# SparkFun_CAN-Bus_Shield.net
KiCad netlist of a schematic drawn in EAGLE
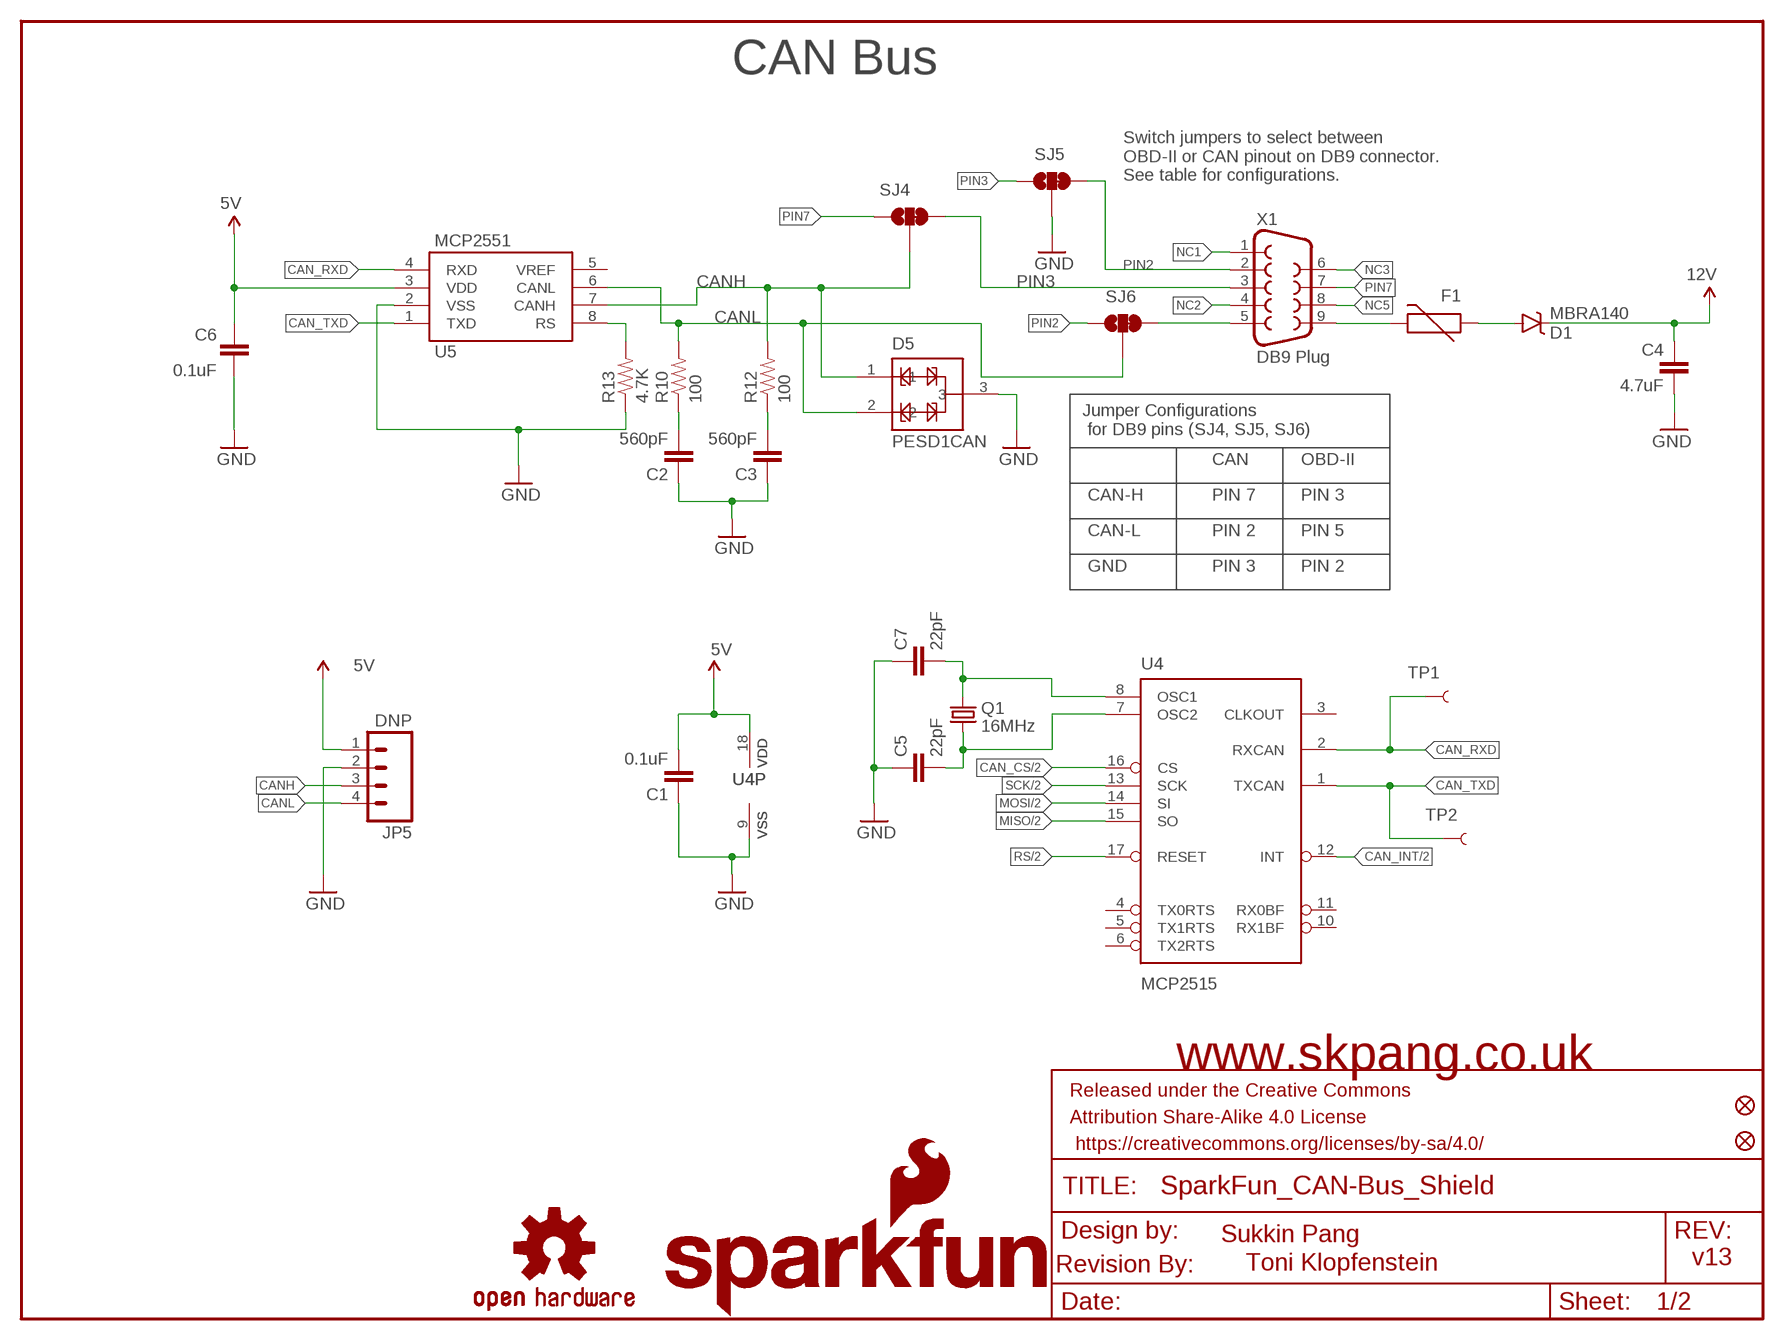
[diagram p0: schematic, sheet 1]
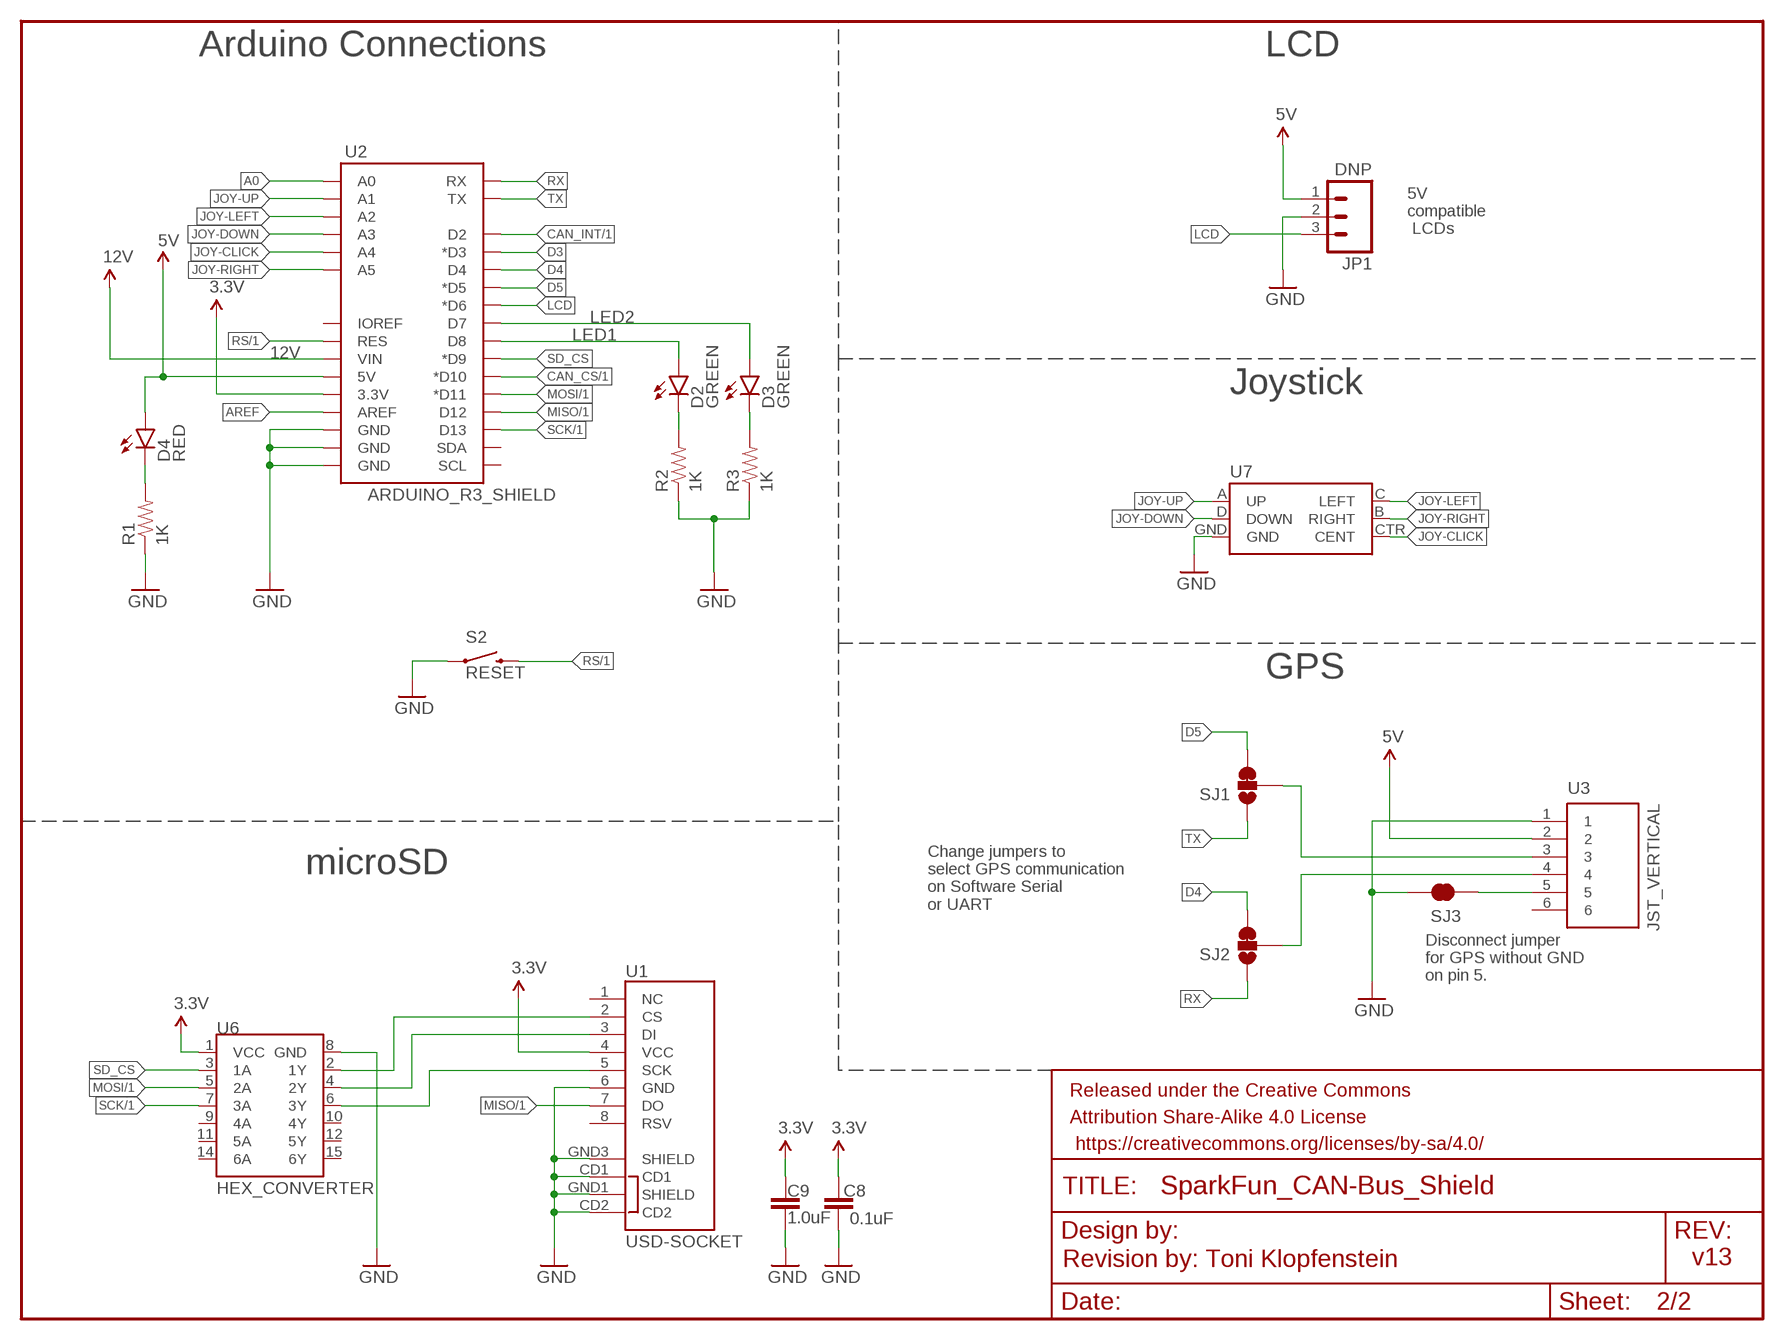
[diagram p1: schematic, sheet 2]

(export (version "E")
  (design (tool "Eeschema 10.0.6"))
  (components
    (comp (ref "C1")
      (value "0.1uF")
      (footprint "eagle-import:0603-CAP")
      (libsource (lib "eagle-import") (part "0.1UF-25V(+80/-20%)(0603)"))
    )
    (comp (ref "C2")
      (value "560pF")
      (footprint "eagle-import:0603-CAP")
      (libsource (lib "eagle-import") (part "560PF-50V-5%(0603)"))
    )
    (comp (ref "C3")
      (value "560pF")
      (footprint "eagle-import:0603-CAP")
      (libsource (lib "eagle-import") (part "560PF-50V-5%(0603)"))
    )
    (comp (ref "C4")
      (value "4.7uF")
      (footprint "eagle-import:0603-CAP")
      (libsource (lib "eagle-import") (part "4.7UF-6.3V-10%(0603)0603"))
    )
    (comp (ref "C5")
      (value "22pF")
      (footprint "eagle-import:0603-CAP")
      (libsource (lib "eagle-import") (part "22PF-50V-5%(0603)"))
    )
    (comp (ref "C6")
      (value "0.1uF")
      (footprint "eagle-import:0603-CAP")
      (libsource (lib "eagle-import") (part "0.1UF-25V(+80/-20%)(0603)"))
    )
    (comp (ref "C7")
      (value "22pF")
      (footprint "eagle-import:0603-CAP")
      (libsource (lib "eagle-import") (part "22PF-50V-5%(0603)"))
    )
    (comp (ref "D1")
      (value "MBRA140")
      (footprint "eagle-import:SMA-DIODE")
      (libsource (lib "eagle-import") (part "MBRA140"))
    )
    (comp (ref "D5")
      (value "PESD1CAN")
      (footprint "eagle-import:SOT23-3")
      (libsource (lib "eagle-import") (part "PESD1CAN"))
    )
    (comp (ref "F1")
      (value "PTCTHERMISTOR1206")
      (footprint "eagle-import:PTC-1206")
      (libsource (lib "eagle-import") (part "PTCTHERMISTOR1206"))
    )
    (comp (ref "FRAME1")
      (value "FRAME-LETTER")
      (footprint "eagle-import:CREATIVE_COMMONS")
      (libsource (lib "eagle-import") (part "FRAME-LETTER"))
    )
    (comp (ref "JP2")
      (value "FIDUCIAL1X2")
      (footprint "eagle-import:FIDUCIAL-1X2")
      (libsource (lib "eagle-import") (part "FIDUCIAL1X2"))
    )
    (comp (ref "JP3")
      (value "FIDUCIAL1X2")
      (footprint "eagle-import:FIDUCIAL-1X2")
      (libsource (lib "eagle-import") (part "FIDUCIAL1X2"))
    )
    (comp (ref "JP4")
      (value "SFE_LOGO_NAME_FLAME.1_INCH")
      (footprint "eagle-import:SFE_LOGO_NAME_FLAME_.1")
      (libsource (lib "eagle-import") (part "SFE_LOGO_NAME_FLAME.1_INCH"))
    )
    (comp (ref "JP5")
      (value "DNP")
      (footprint "eagle-import:1X04")
      (libsource (lib "eagle-import") (part "M04PTH"))
    )
    (comp (ref "LOGO1")
      (value "OSHW-LOGOM")
      (footprint "eagle-import:OSHW-LOGO-M")
      (libsource (lib "eagle-import") (part "OSHW-LOGOM"))
    )
    (comp (ref "Q1")
      (value "16MHz")
      (footprint "eagle-import:CRYSTAL-SMD-5X3")
      (libsource (lib "eagle-import") (part "CRYSTAL5X3"))
    )
    (comp (ref "R10")
      (value "100")
      (footprint "eagle-import:0603-RES")
      (libsource (lib "eagle-import") (part "100OHM-1/10W-1%(0603)"))
    )
    (comp (ref "R12")
      (value "100")
      (footprint "eagle-import:0603-RES")
      (libsource (lib "eagle-import") (part "100OHM-1/10W-1%(0603)"))
    )
    (comp (ref "R13")
      (value "4.7K")
      (footprint "eagle-import:0603-RES")
      (libsource (lib "eagle-import") (part "4.7KOHM-1/10W-1%(0603)"))
    )
    (comp (ref "SJ4")
      (value "JUMPER-PAD-3-2OF3_NC_BY_TRACE_SMALL")
      (footprint "eagle-import:PAD-JUMPER-3-2OF3_NC_BY_TRACE_YES_SILK_FULL_BOX")
      (libsource (lib "eagle-import") (part "JUMPER-PAD-3-2OF3_NC_BY_TRACE_SMALL"))
    )
    (comp (ref "SJ5")
      (value "JUMPER-PAD-3-2OF3_NC_BY_TRACE_SMALL")
      (footprint "eagle-import:PAD-JUMPER-3-2OF3_NC_BY_TRACE_YES_SILK_FULL_BOX")
      (libsource (lib "eagle-import") (part "JUMPER-PAD-3-2OF3_NC_BY_TRACE_SMALL"))
    )
    (comp (ref "SJ6")
      (value "JUMPER-PAD-3-2OF3_NC_BY_TRACE_SMALL")
      (footprint "eagle-import:PAD-JUMPER-3-2OF3_NC_BY_TRACE_YES_SILK_FULL_BOX")
      (libsource (lib "eagle-import") (part "JUMPER-PAD-3-2OF3_NC_BY_TRACE_SMALL"))
    )
    (comp (ref "TP1")
      (value "TEST-POINT3X5")
      (footprint "eagle-import:PAD.03X.05")
      (libsource (lib "eagle-import") (part "TEST-POINT3X5"))
    )
    (comp (ref "TP2")
      (value "TEST-POINT3X5")
      (footprint "eagle-import:PAD.03X.05")
      (libsource (lib "eagle-import") (part "TEST-POINT3X5"))
    )
    (comp (ref "U$1")
      (value "REVISION")
      (footprint "eagle-import:REVISION")
      (libsource (lib "eagle-import") (part "REVISION"))
    )
    (comp (ref "U4")
      (value "MCP2515")
      (footprint "eagle-import:SO-18W")
      (libsource (lib "eagle-import") (part "MCP2510SO"))
    )
    (comp (ref "U5")
      (value "MCP2551")
      (footprint "eagle-import:SO08")
      (libsource (lib "eagle-import") (part "MCP2551"))
    )
    (comp (ref "X1")
      (value "DB9 Plug")
      (footprint "eagle-import:DB9_MALE")
      (libsource (lib "eagle-import") (part "DB9MALE"))
    )
    (comp (ref "C8")
      (value "0.1uF")
      (footprint "eagle-import:0603-CAP")
      (libsource (lib "eagle-import") (part "0.1UF-25V(+80/-20%)(0603)"))
    )
    (comp (ref "C9")
      (value "1.0uF")
      (footprint "eagle-import:0603-CAP")
      (libsource (lib "eagle-import") (part "1.0UF-16V-10%(0603)"))
    )
    (comp (ref "D2")
      (value "GREEN")
      (footprint "eagle-import:LED-0603")
      (libsource (lib "eagle-import") (part "LED-GREEN0603"))
    )
    (comp (ref "D3")
      (value "GREEN")
      (footprint "eagle-import:LED-0603")
      (libsource (lib "eagle-import") (part "LED-GREEN0603"))
    )
    (comp (ref "D4")
      (value "RED")
      (footprint "eagle-import:LED-0603")
      (libsource (lib "eagle-import") (part "LED-RED0603"))
    )
    (comp (ref "FRAME2")
      (value "FRAME-LETTERNO_PACKAGE")
      (footprint "eagle-import:DUMMY")
      (fields (field (name "DESIGNER") "Sukkin Pang and Ryan Owens") (field (name "VERSION") "v13"))
      (libsource (lib "eagle-import") (part "FRAME-LETTERNO_PACKAGE"))
    )
    (comp (ref "JP1")
      (value "DNP")
      (footprint "eagle-import:MOLEX-1X3_LOCK")
      (libsource (lib "eagle-import") (part "M03POLAR_LOCK"))
    )
    (comp (ref "R1")
      (value "1K")
      (footprint "eagle-import:0603-RES")
      (libsource (lib "eagle-import") (part "1KOHM-1/10W-1%(0603)"))
    )
    (comp (ref "R2")
      (value "1K")
      (footprint "eagle-import:0603-RES")
      (libsource (lib "eagle-import") (part "1KOHM-1/10W-1%(0603)"))
    )
    (comp (ref "R3")
      (value "1K")
      (footprint "eagle-import:0603-RES")
      (libsource (lib "eagle-import") (part "1KOHM-1/10W-1%(0603)"))
    )
    (comp (ref "S2")
      (value "RESET")
      (footprint "eagle-import:TACTILE-SWITCH-SMD")
      (libsource (lib "eagle-import") (part "SWITCH-MOMENTARY-2SMD"))
    )
    (comp (ref "SJ1")
      (value "JUMPER-PAD-3-2OF3_NC_BY_TRACE_SMALL")
      (footprint "eagle-import:PAD-JUMPER-3-2OF3_NC_BY_TRACE_YES_SILK_FULL_BOX")
      (libsource (lib "eagle-import") (part "JUMPER-PAD-3-2OF3_NC_BY_TRACE_SMALL"))
    )
    (comp (ref "SJ2")
      (value "JUMPER-PAD-3-2OF3_NC_BY_TRACE_SMALL")
      (footprint "eagle-import:PAD-JUMPER-3-2OF3_NC_BY_TRACE_YES_SILK_FULL_BOX")
      (libsource (lib "eagle-import") (part "JUMPER-PAD-3-2OF3_NC_BY_TRACE_SMALL"))
    )
    (comp (ref "SJ3")
      (value "JUMPER-PAD-2-NC_BY_TRACE")
      (footprint "eagle-import:PAD-JUMPER-2-NC_BY_TRACE_YES_SILK")
      (libsource (lib "eagle-import") (part "JUMPER-PAD-2-NC_BY_TRACE"))
    )
    (comp (ref "U1")
      (value "USD-SOCKET")
      (footprint "eagle-import:MICROSD_1_1")
      (libsource (lib "eagle-import") (part "USD-SOCKET"))
    )
    (comp (ref "U2")
      (value "ARDUINO_R3_SHIELD")
      (footprint "eagle-import:UNO_R3_SHIELD")
      (libsource (lib "eagle-import") (part "ARDUINO_R3_SHIELD"))
    )
    (comp (ref "U3")
      (value "JST_VERTICAL")
      (footprint "eagle-import:JST-6-SMD-VERT-1.0MM")
      (libsource (lib "eagle-import") (part "JST_VERTICAL"))
    )
    (comp (ref "U6")
      (value "HEX_CONVERTER")
      (footprint "eagle-import:SO016")
      (libsource (lib "eagle-import") (part "HEX_CONVERTER"))
    )
    (comp (ref "U7")
      (value "JOYSTICK_MINI")
      (footprint "eagle-import:JOYSTICK_MINI")
      (libsource (lib "eagle-import") (part "JOYSTICK_MINI"))
    )
  )
  (nets
    (net (code "1") (name "3.3V") (class "Default")
      (node (ref "C8") (pin "2") (pinfunction "2_2") (pintype "passive"))
      (node (ref "C9") (pin "1") (pinfunction "1_1") (pintype "passive"))
      (node (ref "U1") (pin "4") (pinfunction "VCC_4") (pintype "bidirectional"))
      (node (ref "U2") (pin "3.3V") (pinfunction "3.3V_3.3V") (pintype "bidirectional"))
      (node (ref "U6") (pin "1") (pinfunction "VCC_1") (pintype "bidirectional"))
    )
    (net (code "2") (name "5V") (class "Default")
      (node (ref "C1") (pin "2") (pinfunction "2_2") (pintype "passive"))
      (node (ref "C6") (pin "2") (pinfunction "2_2") (pintype "passive"))
      (node (ref "D4") (pin "A") (pinfunction "A_A") (pintype "passive"))
      (node (ref "JP1") (pin "1") (pinfunction "1_1") (pintype "passive"))
      (node (ref "JP5") (pin "1") (pinfunction "1_1") (pintype "passive"))
      (node (ref "U2") (pin "5V") (pinfunction "5V_5V") (pintype "bidirectional"))
      (node (ref "U3") (pin "2") (pinfunction "2_2") (pintype "bidirectional"))
      (node (ref "U4") (pin "18") (pinfunction "VDD_18") (pintype "power_in"))
      (node (ref "U5") (pin "3") (pinfunction "VDD_3") (pintype "bidirectional"))
    )
    (net (code "3") (name "12V") (class "Default")
      (node (ref "C4") (pin "1") (pinfunction "1_1") (pintype "passive"))
      (node (ref "D1") (pin "C") (pinfunction "C_C") (pintype "passive"))
      (node (ref "U2") (pin "VIN") (pinfunction "VIN_VIN") (pintype "bidirectional"))
    )
    (net (code "4") (name "A0") (class "Default")
      (node (ref "U2") (pin "A0") (pinfunction "A0_A0") (pintype "bidirectional"))
    )
    (net (code "5") (name "AREF") (class "Default")
      (node (ref "U2") (pin "AREF") (pinfunction "AREF_AREF") (pintype "bidirectional"))
    )
    (net (code "6") (name "CANH") (class "Default")
      (node (ref "D5") (pin "1") (pinfunction "1_1") (pintype "bidirectional"))
      (node (ref "JP5") (pin "3") (pinfunction "3_3") (pintype "passive"))
      (node (ref "R12") (pin "2") (pinfunction "2_2") (pintype "passive"))
      (node (ref "SJ4") (pin "2") (pinfunction "2_2") (pintype "passive"))
      (node (ref "U5") (pin "7") (pinfunction "CANH_7") (pintype "bidirectional"))
    )
    (net (code "7") (name "CANL") (class "Default")
      (node (ref "D5") (pin "2") (pinfunction "2_2") (pintype "bidirectional"))
      (node (ref "JP5") (pin "4") (pinfunction "4_4") (pintype "passive"))
      (node (ref "R10") (pin "2") (pinfunction "2_2") (pintype "passive"))
      (node (ref "SJ6") (pin "2") (pinfunction "2_2") (pintype "passive"))
      (node (ref "U5") (pin "6") (pinfunction "CANL_6") (pintype "bidirectional"))
    )
    (net (code "8") (name "CAN_CS") (class "Default")
      (node (ref "U2") (pin "D10") (pinfunction "*D10_D10") (pintype "bidirectional"))
      (node (ref "U4") (pin "16") (pinfunction "CS_16") (pintype "input"))
    )
    (net (code "9") (name "CAN_INT") (class "Default")
      (node (ref "U2") (pin "D2") (pinfunction "D2_D2") (pintype "bidirectional"))
      (node (ref "U4") (pin "12") (pinfunction "INT_12") (pintype "output"))
    )
    (net (code "10") (name "CAN_RXD") (class "Default")
      (node (ref "TP1") (pin "P$1") (pinfunction "1_P$1") (pintype "bidirectional"))
      (node (ref "U4") (pin "2") (pinfunction "RXCAN_2") (pintype "input"))
      (node (ref "U5") (pin "4") (pinfunction "RXD_4") (pintype "bidirectional"))
    )
    (net (code "11") (name "CAN_TXD") (class "Default")
      (node (ref "TP2") (pin "P$1") (pinfunction "1_P$1") (pintype "bidirectional"))
      (node (ref "U4") (pin "1") (pinfunction "TXCAN_1") (pintype "output"))
      (node (ref "U5") (pin "1") (pinfunction "TXD_1") (pintype "bidirectional"))
    )
    (net (code "12") (name "D3") (class "Default")
      (node (ref "U2") (pin "D3") (pinfunction "*D3_D3") (pintype "bidirectional"))
    )
    (net (code "13") (name "D4") (class "Default")
      (node (ref "SJ2") (pin "3") (pinfunction "3_3") (pintype "passive"))
      (node (ref "U2") (pin "D4") (pinfunction "D4_D4") (pintype "bidirectional"))
    )
    (net (code "14") (name "D5") (class "Default")
      (node (ref "SJ1") (pin "3") (pinfunction "3_3") (pintype "passive"))
      (node (ref "U2") (pin "D5") (pinfunction "*D5_D5") (pintype "bidirectional"))
    )
    (net (code "15") (name "GND") (class "Default")
      (node (ref "C1") (pin "1") (pinfunction "1_1") (pintype "passive"))
      (node (ref "C2") (pin "1") (pinfunction "1_1") (pintype "passive"))
      (node (ref "C3") (pin "1") (pinfunction "1_1") (pintype "passive"))
      (node (ref "C4") (pin "2") (pinfunction "2_2") (pintype "passive"))
      (node (ref "C5") (pin "1") (pinfunction "1_1") (pintype "passive"))
      (node (ref "C6") (pin "1") (pinfunction "1_1") (pintype "passive"))
      (node (ref "C7") (pin "1") (pinfunction "1_1") (pintype "passive"))
      (node (ref "C8") (pin "1") (pinfunction "1_1") (pintype "passive"))
      (node (ref "C9") (pin "2") (pinfunction "2_2") (pintype "passive"))
      (node (ref "D5") (pin "3") (pinfunction "3_3") (pintype "bidirectional"))
      (node (ref "JP1") (pin "2") (pinfunction "2_2") (pintype "passive"))
      (node (ref "JP5") (pin "2") (pinfunction "2_2") (pintype "passive"))
      (node (ref "R1") (pin "1") (pinfunction "1_1") (pintype "passive"))
      (node (ref "R13") (pin "1") (pinfunction "1_1") (pintype "passive"))
      (node (ref "R2") (pin "1") (pinfunction "1_1") (pintype "passive"))
      (node (ref "R3") (pin "1") (pinfunction "1_1") (pintype "passive"))
      (node (ref "S2") (pin "1") (pinfunction "1_1") (pintype "passive"))
      (node (ref "SJ3") (pin "2") (pinfunction "2_2") (pintype "passive"))
      (node (ref "SJ5") (pin "2") (pinfunction "2_2") (pintype "passive"))
      (node (ref "U1") (pin "6") (pinfunction "GND_6") (pintype "bidirectional"))
      (node (ref "U1") (pin "CD1") (pinfunction "CD1_CD1") (pintype "bidirectional"))
      (node (ref "U1") (pin "CD2") (pinfunction "CD2_CD2") (pintype "bidirectional"))
      (node (ref "U1") (pin "GND1") (pinfunction "SHIELD_GND1") (pintype "bidirectional"))
      (node (ref "U1") (pin "GND3") (pinfunction "SHIELD_GND3") (pintype "bidirectional"))
      (node (ref "U2") (pin "GND@0") (pinfunction "GND_GND@0") (pintype "bidirectional"))
      (node (ref "U2") (pin "GND@1") (pinfunction "GND_GND@1") (pintype "bidirectional"))
      (node (ref "U2") (pin "GND@2") (pinfunction "GND_GND@2") (pintype "bidirectional"))
      (node (ref "U3") (pin "1") (pinfunction "1_1") (pintype "bidirectional"))
      (node (ref "U4") (pin "9") (pinfunction "VSS_9") (pintype "power_in"))
      (node (ref "U5") (pin "2") (pinfunction "VSS_2") (pintype "bidirectional"))
      (node (ref "U6") (pin "8") (pinfunction "GND_8") (pintype "bidirectional"))
      (node (ref "U7") (pin "GND") (pinfunction "GND_GND") (pintype "bidirectional"))
    )
    (net (code "16") (name "JOY-CLICK") (class "Default")
      (node (ref "U2") (pin "A4") (pinfunction "A4_A4") (pintype "bidirectional"))
      (node (ref "U7") (pin "CTR") (pinfunction "CENT_CTR") (pintype "bidirectional"))
    )
    (net (code "17") (name "JOY-DOWN") (class "Default")
      (node (ref "U2") (pin "A3") (pinfunction "A3_A3") (pintype "bidirectional"))
      (node (ref "U7") (pin "D") (pinfunction "DOWN_D") (pintype "bidirectional"))
    )
    (net (code "18") (name "JOY-LEFT") (class "Default")
      (node (ref "U2") (pin "A2") (pinfunction "A2_A2") (pintype "bidirectional"))
      (node (ref "U7") (pin "C") (pinfunction "LEFT_C") (pintype "bidirectional"))
    )
    (net (code "19") (name "JOY-RIGHT") (class "Default")
      (node (ref "U2") (pin "A5") (pinfunction "A5_A5") (pintype "bidirectional"))
      (node (ref "U7") (pin "B") (pinfunction "RIGHT_B") (pintype "bidirectional"))
    )
    (net (code "20") (name "JOY-UP") (class "Default")
      (node (ref "U2") (pin "A1") (pinfunction "A1_A1") (pintype "bidirectional"))
      (node (ref "U7") (pin "A") (pinfunction "UP_A") (pintype "bidirectional"))
    )
    (net (code "21") (name "LCD") (class "Default")
      (node (ref "JP1") (pin "3") (pinfunction "3_3") (pintype "passive"))
      (node (ref "U2") (pin "D6") (pinfunction "*D6_D6") (pintype "bidirectional"))
    )
    (net (code "22") (name "LED1") (class "Default")
      (node (ref "D2") (pin "A") (pinfunction "A_A") (pintype "passive"))
      (node (ref "U2") (pin "D8") (pinfunction "D8_D8") (pintype "bidirectional"))
    )
    (net (code "23") (name "LED2") (class "Default")
      (node (ref "D3") (pin "A") (pinfunction "A_A") (pintype "passive"))
      (node (ref "U2") (pin "D7") (pinfunction "D7_D7") (pintype "bidirectional"))
    )
    (net (code "24") (name "MISO") (class "Default")
      (node (ref "U1") (pin "7") (pinfunction "DO_7") (pintype "bidirectional"))
      (node (ref "U2") (pin "D12") (pinfunction "D12_D12") (pintype "bidirectional"))
      (node (ref "U4") (pin "15") (pinfunction "SO_15") (pintype "output"))
    )
    (net (code "25") (name "MOSI") (class "Default")
      (node (ref "U2") (pin "D11") (pinfunction "*D11_D11") (pintype "bidirectional"))
      (node (ref "U4") (pin "14") (pinfunction "SI_14") (pintype "input"))
      (node (ref "U6") (pin "5") (pinfunction "2A_5") (pintype "bidirectional"))
    )
    (net (code "26") (name "NC1") (class "Default")
      (node (ref "X1") (pin "1") (pinfunction "1_1") (pintype "passive"))
    )
    (net (code "27") (name "NC2") (class "Default")
      (node (ref "X1") (pin "4") (pinfunction "4_4") (pintype "passive"))
    )
    (net (code "28") (name "NC3") (class "Default")
      (node (ref "X1") (pin "6") (pinfunction "6_6") (pintype "passive"))
    )
    (net (code "29") (name "NC5") (class "Default")
      (node (ref "X1") (pin "8") (pinfunction "8_8") (pintype "passive"))
    )
    (net (code "30") (name "Net-(C2-Pad2)") (class "Default")
      (node (ref "C2") (pin "2") (pinfunction "2_2") (pintype "passive"))
      (node (ref "R10") (pin "1") (pinfunction "1_1") (pintype "passive"))
    )
    (net (code "31") (name "Net-(C3-Pad2)") (class "Default")
      (node (ref "C3") (pin "2") (pinfunction "2_2") (pintype "passive"))
      (node (ref "R12") (pin "1") (pinfunction "1_1") (pintype "passive"))
    )
    (net (code "32") (name "Net-(D1-PadA)") (class "Default")
      (node (ref "D1") (pin "A") (pinfunction "A_A") (pintype "passive"))
      (node (ref "F1") (pin "1") (pinfunction "1_1") (pintype "bidirectional"))
    )
    (net (code "33") (name "Net-(D2-PadC)") (class "Default")
      (node (ref "D2") (pin "C") (pinfunction "C_C") (pintype "passive"))
      (node (ref "R2") (pin "2") (pinfunction "2_2") (pintype "passive"))
    )
    (net (code "34") (name "Net-(D3-PadC)") (class "Default")
      (node (ref "D3") (pin "C") (pinfunction "C_C") (pintype "passive"))
      (node (ref "R3") (pin "2") (pinfunction "2_2") (pintype "passive"))
    )
    (net (code "35") (name "Net-(D4-PadC)") (class "Default")
      (node (ref "D4") (pin "C") (pinfunction "C_C") (pintype "passive"))
      (node (ref "R1") (pin "2") (pinfunction "2_2") (pintype "passive"))
    )
    (net (code "36") (name "Net-(F1-Pad2)") (class "Default")
      (node (ref "F1") (pin "2") (pinfunction "2_2") (pintype "bidirectional"))
      (node (ref "X1") (pin "9") (pinfunction "9_9") (pintype "passive"))
    )
    (net (code "37") (name "Net-(Q1-2)") (class "Default")
      (node (ref "C7") (pin "2") (pinfunction "2_2") (pintype "passive"))
      (node (ref "Q1") (pin "3") (pinfunction "2_3") (pintype "passive"))
      (node (ref "U4") (pin "8") (pinfunction "OSC1_8") (pintype "input"))
    )
    (net (code "38") (name "Net-(SJ1-Pad2)") (class "Default")
      (node (ref "SJ1") (pin "2") (pinfunction "2_2") (pintype "passive"))
      (node (ref "U3") (pin "3") (pinfunction "3_3") (pintype "bidirectional"))
    )
    (net (code "39") (name "Net-(SJ2-Pad2)") (class "Default")
      (node (ref "SJ2") (pin "2") (pinfunction "2_2") (pintype "passive"))
      (node (ref "U3") (pin "4") (pinfunction "4_4") (pintype "bidirectional"))
    )
    (net (code "40") (name "Net-(SJ3-Pad1)") (class "Default")
      (node (ref "SJ3") (pin "1") (pinfunction "1_1") (pintype "passive"))
      (node (ref "U3") (pin "5") (pinfunction "5_5") (pintype "bidirectional"))
    )
    (net (code "41") (name "Net-(SJ6-Pad3)") (class "Default")
      (node (ref "SJ6") (pin "3") (pinfunction "3_3") (pintype "passive"))
      (node (ref "X1") (pin "5") (pinfunction "5_5") (pintype "passive"))
    )
    (net (code "42") (name "Net-(U1-CS)") (class "Default")
      (node (ref "U1") (pin "2") (pinfunction "CS_2") (pintype "bidirectional"))
      (node (ref "U6") (pin "2") (pinfunction "1Y_2") (pintype "bidirectional"))
    )
    (net (code "43") (name "Net-(U1-DI)") (class "Default")
      (node (ref "U1") (pin "3") (pinfunction "DI_3") (pintype "bidirectional"))
      (node (ref "U6") (pin "4") (pinfunction "2Y_4") (pintype "bidirectional"))
    )
    (net (code "44") (name "Net-(U1-SCK)") (class "Default")
      (node (ref "U1") (pin "5") (pinfunction "SCK_5") (pintype "bidirectional"))
      (node (ref "U6") (pin "6") (pinfunction "3Y_6") (pintype "bidirectional"))
    )
    (net (code "45") (name "Net-(U4A-OSC2)") (class "Default")
      (node (ref "C5") (pin "2") (pinfunction "2_2") (pintype "passive"))
      (node (ref "Q1") (pin "1") (pinfunction "1_1") (pintype "passive"))
      (node (ref "U4") (pin "7") (pinfunction "OSC2_7") (pintype "output"))
    )
    (net (code "46") (name "Net-(U5-RS)") (class "Default")
      (node (ref "R13") (pin "2") (pinfunction "2_2") (pintype "passive"))
      (node (ref "U5") (pin "8") (pinfunction "RS_8") (pintype "bidirectional"))
    )
    (net (code "47") (name "PIN2") (class "Default")
      (node (ref "SJ5") (pin "3") (pinfunction "3_3") (pintype "passive"))
      (node (ref "SJ6") (pin "1") (pinfunction "1_1") (pintype "passive"))
      (node (ref "X1") (pin "2") (pinfunction "2_2") (pintype "passive"))
    )
    (net (code "48") (name "PIN3") (class "Default")
      (node (ref "SJ4") (pin "3") (pinfunction "3_3") (pintype "passive"))
      (node (ref "SJ5") (pin "1") (pinfunction "1_1") (pintype "passive"))
      (node (ref "X1") (pin "3") (pinfunction "3_3") (pintype "passive"))
    )
    (net (code "49") (name "PIN7") (class "Default")
      (node (ref "SJ4") (pin "1") (pinfunction "1_1") (pintype "passive"))
      (node (ref "X1") (pin "7") (pinfunction "7_7") (pintype "passive"))
    )
    (net (code "50") (name "RS") (class "Default")
      (node (ref "S2") (pin "3") (pinfunction "2_3") (pintype "passive"))
      (node (ref "U2") (pin "RES") (pinfunction "RES_RES") (pintype "bidirectional"))
      (node (ref "U4") (pin "17") (pinfunction "RESET_17") (pintype "input"))
    )
    (net (code "51") (name "RX") (class "Default")
      (node (ref "SJ2") (pin "1") (pinfunction "1_1") (pintype "passive"))
      (node (ref "U2") (pin "RX") (pinfunction "RX_RX") (pintype "bidirectional"))
    )
    (net (code "52") (name "SCK") (class "Default")
      (node (ref "U2") (pin "D13") (pinfunction "D13_D13") (pintype "bidirectional"))
      (node (ref "U4") (pin "13") (pinfunction "SCK_13") (pintype "input"))
      (node (ref "U6") (pin "7") (pinfunction "3A_7") (pintype "bidirectional"))
    )
    (net (code "53") (name "SD_CS") (class "Default")
      (node (ref "U2") (pin "D9") (pinfunction "*D9_D9") (pintype "bidirectional"))
      (node (ref "U6") (pin "3") (pinfunction "1A_3") (pintype "bidirectional"))
    )
    (net (code "54") (name "TX") (class "Default")
      (node (ref "SJ1") (pin "1") (pinfunction "1_1") (pintype "passive"))
      (node (ref "U2") (pin "TX") (pinfunction "TX_TX") (pintype "bidirectional"))
    )
    (net (code "55") (name "unconnected-(U1-NC-Pad1)") (class "Default")
      (node (ref "U1") (pin "1") (pinfunction "NC_1") (pintype "bidirectional"))
    )
    (net (code "56") (name "unconnected-(U1-RSV-Pad8)") (class "Default")
      (node (ref "U1") (pin "8") (pinfunction "RSV_8") (pintype "bidirectional"))
    )
    (net (code "57") (name "unconnected-(U2-PadIOREF)") (class "Default")
      (node (ref "U2") (pin "IOREF") (pinfunction "IOREF_IOREF") (pintype "bidirectional"))
    )
    (net (code "58") (name "unconnected-(U2-PadSCL)") (class "Default")
      (node (ref "U2") (pin "SCL") (pinfunction "SCL_SCL") (pintype "bidirectional"))
    )
    (net (code "59") (name "unconnected-(U2-PadSDA)") (class "Default")
      (node (ref "U2") (pin "SDA") (pinfunction "SDA_SDA") (pintype "bidirectional"))
    )
    (net (code "60") (name "unconnected-(U3-Pad6)") (class "Default")
      (node (ref "U3") (pin "6") (pinfunction "6_6") (pintype "bidirectional"))
    )
    (net (code "61") (name "unconnected-(U4A-CLKOUT-Pad3)") (class "Default")
      (node (ref "U4") (pin "3") (pinfunction "CLKOUT_3") (pintype "output"))
    )
    (net (code "62") (name "unconnected-(U4A-RX0BF-Pad11)") (class "Default")
      (node (ref "U4") (pin "11") (pinfunction "RX0BF_11") (pintype "output"))
    )
    (net (code "63") (name "unconnected-(U4A-RX1BF-Pad10)") (class "Default")
      (node (ref "U4") (pin "10") (pinfunction "RX1BF_10") (pintype "output"))
    )
    (net (code "64") (name "unconnected-(U4A-TX0RTS-Pad4)") (class "Default")
      (node (ref "U4") (pin "4") (pinfunction "TX0RTS_4") (pintype "input"))
    )
    (net (code "65") (name "unconnected-(U4A-TX1RTS-Pad5)") (class "Default")
      (node (ref "U4") (pin "5") (pinfunction "TX1RTS_5") (pintype "input"))
    )
    (net (code "66") (name "unconnected-(U4A-TX2RTS-Pad6)") (class "Default")
      (node (ref "U4") (pin "6") (pinfunction "TX2RTS_6") (pintype "input"))
    )
    (net (code "67") (name "unconnected-(U5-VREF-Pad5)") (class "Default")
      (node (ref "U5") (pin "5") (pinfunction "VREF_5") (pintype "bidirectional"))
    )
    (net (code "68") (name "unconnected-(U6-4A-Pad9)") (class "Default")
      (node (ref "U6") (pin "9") (pinfunction "4A_9") (pintype "bidirectional"))
    )
    (net (code "69") (name "unconnected-(U6-4Y-Pad10)") (class "Default")
      (node (ref "U6") (pin "10") (pinfunction "4Y_10") (pintype "bidirectional"))
    )
    (net (code "70") (name "unconnected-(U6-5A-Pad11)") (class "Default")
      (node (ref "U6") (pin "11") (pinfunction "5A_11") (pintype "bidirectional"))
    )
    (net (code "71") (name "unconnected-(U6-5Y-Pad12)") (class "Default")
      (node (ref "U6") (pin "12") (pinfunction "5Y_12") (pintype "bidirectional"))
    )
    (net (code "72") (name "unconnected-(U6-6A-Pad14)") (class "Default")
      (node (ref "U6") (pin "14") (pinfunction "6A_14") (pintype "bidirectional"))
    )
    (net (code "73") (name "unconnected-(U6-6Y-Pad15)") (class "Default")
      (node (ref "U6") (pin "15") (pinfunction "6Y_15") (pintype "bidirectional"))
    )
  )
)
